# 7_-H3_POWER.net
KiCad netlist of a schematic drawn in Altium Designer
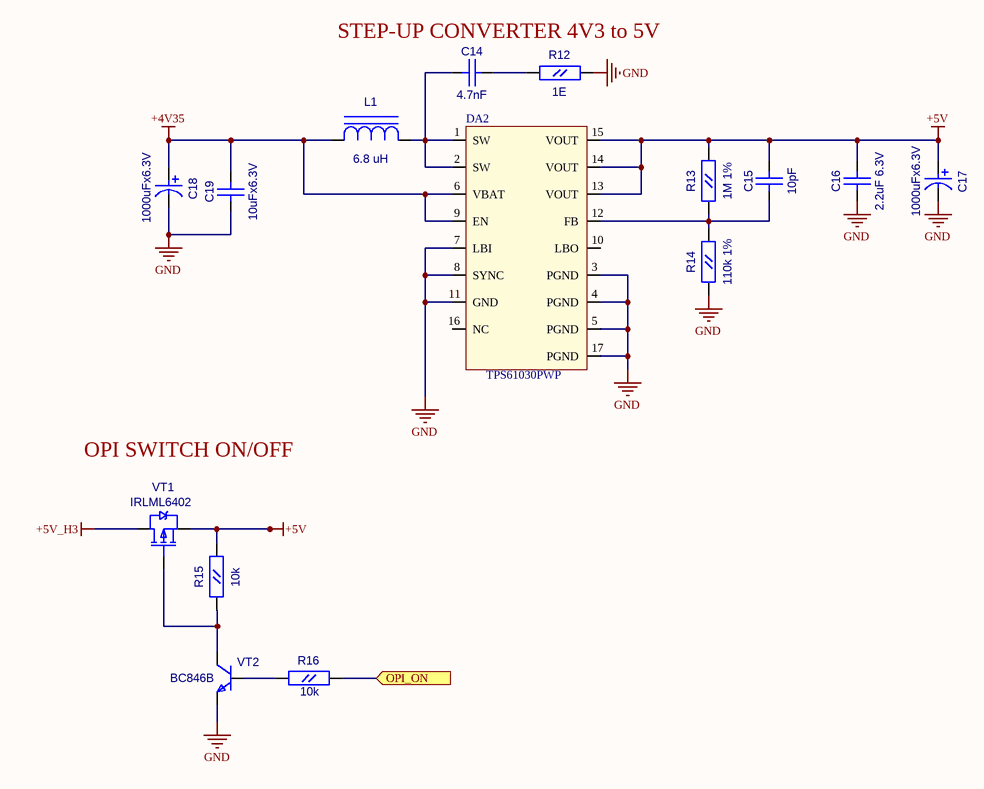
[diagram p0: [7]-H3_POWER.SchDoc]

(export (version "E")
  (design (tool "Eeschema 10.0.6"))
  (components
    (comp (ref "C14")
      (value "4.7nF")
      (footprint "CC0603")
      (description "CC0603")
      (libsource (lib "gprs_modem_2") (part "CC0603"))
    )
    (comp (ref "C15")
      (value "10pF")
      (footprint "CC0603")
      (description "CC0603")
      (libsource (lib "gprs_modem_2") (part "CC0603"))
    )
    (comp (ref "C16")
      (value "2.2uF 6.3V")
      (footprint "CC0805")
      (description "CC0805")
      (libsource (lib "gprs_modem_2") (part "CC0805"))
    )
    (comp (ref "C17")
      (value "1000uFx6.3V")
      (footprint "CC8X3.5")
      (description "CAP0.35")
      (libsource (lib "gprs_modem_2") (part "CAP0.35"))
    )
    (comp (ref "C18")
      (value "1000uFx6.3V")
      (footprint "CC8X3.5")
      (description "CAP0.35")
      (libsource (lib "gprs_modem_2") (part "CAP0.35"))
    )
    (comp (ref "C19")
      (value "10uFx6.3V")
      (footprint "CC0805")
      (description "CC0805")
      (libsource (lib "gprs_modem_2") (part "CC0805"))
    )
    (comp (ref "DA2")
      (value "TPS61030PWP")
      (footprint "R-PDSO-G16")
      (description "Boost converter")
      (libsource (lib "gprs_modem") (part "TPS61030PWP"))
    )
    (comp (ref "L1")
      (value "6.8 uH")
      (footprint "SDR0805")
      (description "SDR0805")
      (libsource (lib "gprs_modem_2") (part "SDR0805"))
    )
    (comp (ref "R12")
      (value "1E")
      (footprint "RC0603")
      (description "RC0603")
      (libsource (lib "gprs_modem_2") (part "RC0603"))
    )
    (comp (ref "R13")
      (value "1M 1%")
      (footprint "RC0603")
      (description "RC0603")
      (libsource (lib "gprs_modem_2") (part "RC0603"))
    )
    (comp (ref "R14")
      (value "110k 1%")
      (footprint "RC0603")
      (description "RC0603")
      (libsource (lib "gprs_modem_2") (part "RC0603"))
    )
    (comp (ref "R15")
      (value "10k")
      (footprint "RC0603")
      (description "RC0603")
      (libsource (lib "gprs_modem_2") (part "RC0603"))
    )
    (comp (ref "R16")
      (value "10k")
      (footprint "RC0603")
      (description "RC0603")
      (libsource (lib "fizik_lib") (part "RC0603"))
    )
    (comp (ref "VT1")
      (value "IRLML6402")
      (footprint "SOT-23(123)")
      (description "HEXFET Power MOSFET")
      (libsource (lib "gprs_modem_2") (part "IRLML6402"))
    )
    (comp (ref "VT2")
      (value "BC846B")
      (footprint "SOT-23(123)")
      (description "BC846BLT1")
      (libsource (lib "gprs_modem_2") (part "BC846BLT1"))
    )
  )
  (nets
    (net (code "1") (name "+4V35") (class "Default")
      (node (ref "C18") (pin "1") (pintype "passive"))
      (node (ref "C19") (pin "2") (pinfunction "B_2") (pintype "passive"))
      (node (ref "DA2") (pin "6") (pinfunction "VBAT_6") (pintype "passive"))
      (node (ref "DA2") (pin "9") (pinfunction "EN_9") (pintype "passive"))
      (node (ref "L1") (pin "1") (pinfunction "C_1") (pintype "passive"))
    )
    (net (code "2") (name "+5V") (class "Default")
      (node (ref "C15") (pin "2") (pinfunction "B_2") (pintype "passive"))
      (node (ref "C16") (pin "2") (pinfunction "B_2") (pintype "passive"))
      (node (ref "C17") (pin "1") (pintype "passive"))
      (node (ref "DA2") (pin "13") (pinfunction "VOUT_13") (pintype "passive"))
      (node (ref "DA2") (pin "14") (pinfunction "VOUT_14") (pintype "passive"))
      (node (ref "DA2") (pin "15") (pinfunction "VOUT_15") (pintype "passive"))
      (node (ref "R13") (pin "2") (pinfunction "B_2") (pintype "passive"))
      (node (ref "R15") (pin "2") (pinfunction "B_2") (pintype "passive"))
      (node (ref "VT1") (pin "2") (pinfunction "S_2") (pintype "passive"))
    )
    (net (code "3") (name "+5V_H3") (class "Default")
      (node (ref "VT1") (pin "3") (pinfunction "D_3") (pintype "passive"))
    )
    (net (code "4") (name "/OPI_ON") (class "Default")
      (node (ref "R16") (pin "2") (pinfunction "B_2") (pintype "passive"))
    )
    (net (code "5") (name "GND") (class "Default")
      (node (ref "C16") (pin "1") (pinfunction "A_1") (pintype "passive"))
      (node (ref "C17") (pin "2") (pintype "passive"))
      (node (ref "C18") (pin "2") (pintype "passive"))
      (node (ref "C19") (pin "1") (pinfunction "A_1") (pintype "passive"))
      (node (ref "DA2") (pin "11") (pinfunction "GND_11") (pintype "passive"))
      (node (ref "DA2") (pin "17") (pinfunction "PGND_17") (pintype "passive"))
      (node (ref "DA2") (pin "3") (pinfunction "PGND_3") (pintype "passive"))
      (node (ref "DA2") (pin "4") (pinfunction "PGND_4") (pintype "passive"))
      (node (ref "DA2") (pin "5") (pinfunction "PGND_5") (pintype "passive"))
      (node (ref "DA2") (pin "7") (pinfunction "LBI_7") (pintype "passive"))
      (node (ref "DA2") (pin "8") (pinfunction "SYNC_8") (pintype "passive"))
      (node (ref "R12") (pin "2") (pinfunction "B_2") (pintype "passive"))
      (node (ref "R14") (pin "1") (pinfunction "A_1") (pintype "passive"))
      (node (ref "VT2") (pin "2") (pinfunction "E_2") (pintype "passive"))
    )
    (net (code "6") (name "Net-(C14-A)") (class "Default")
      (node (ref "C14") (pin "1") (pinfunction "A_1") (pintype "passive"))
      (node (ref "DA2") (pin "1") (pinfunction "SW_1") (pintype "passive"))
      (node (ref "DA2") (pin "2") (pinfunction "SW_2") (pintype "passive"))
      (node (ref "L1") (pin "2") (pinfunction "A_2") (pintype "passive"))
    )
    (net (code "7") (name "Net-(C14-B)") (class "Default")
      (node (ref "C14") (pin "2") (pinfunction "B_2") (pintype "passive"))
      (node (ref "R12") (pin "1") (pinfunction "A_1") (pintype "passive"))
    )
    (net (code "8") (name "Net-(C15-A)") (class "Default")
      (node (ref "C15") (pin "1") (pinfunction "A_1") (pintype "passive"))
      (node (ref "DA2") (pin "12") (pinfunction "FB_12") (pintype "passive"))
      (node (ref "R13") (pin "1") (pinfunction "A_1") (pintype "passive"))
      (node (ref "R14") (pin "2") (pinfunction "B_2") (pintype "passive"))
    )
    (net (code "9") (name "Net-(R15-A)") (class "Default")
      (node (ref "R15") (pin "1") (pinfunction "A_1") (pintype "passive"))
      (node (ref "VT1") (pin "1") (pinfunction "G_1") (pintype "passive"))
      (node (ref "VT2") (pin "3") (pinfunction "C_3") (pintype "passive"))
    )
    (net (code "10") (name "Net-(R16-A)") (class "Default")
      (node (ref "R16") (pin "1") (pinfunction "A_1") (pintype "passive"))
      (node (ref "VT2") (pin "1") (pinfunction "B_1") (pintype "passive"))
    )
    (net (code "11") (name "unconnected-(DA2-LBO-Pad10)") (class "Default")
      (node (ref "DA2") (pin "10") (pinfunction "LBO_10") (pintype "passive"))
    )
    (net (code "12") (name "unconnected-(DA2-NC-Pad16)") (class "Default")
      (node (ref "DA2") (pin "16") (pinfunction "NC_16") (pintype "passive"))
    )
  )
)
